# Sheet_Receive.net
KiCad netlist of a schematic drawn in Altium Designer
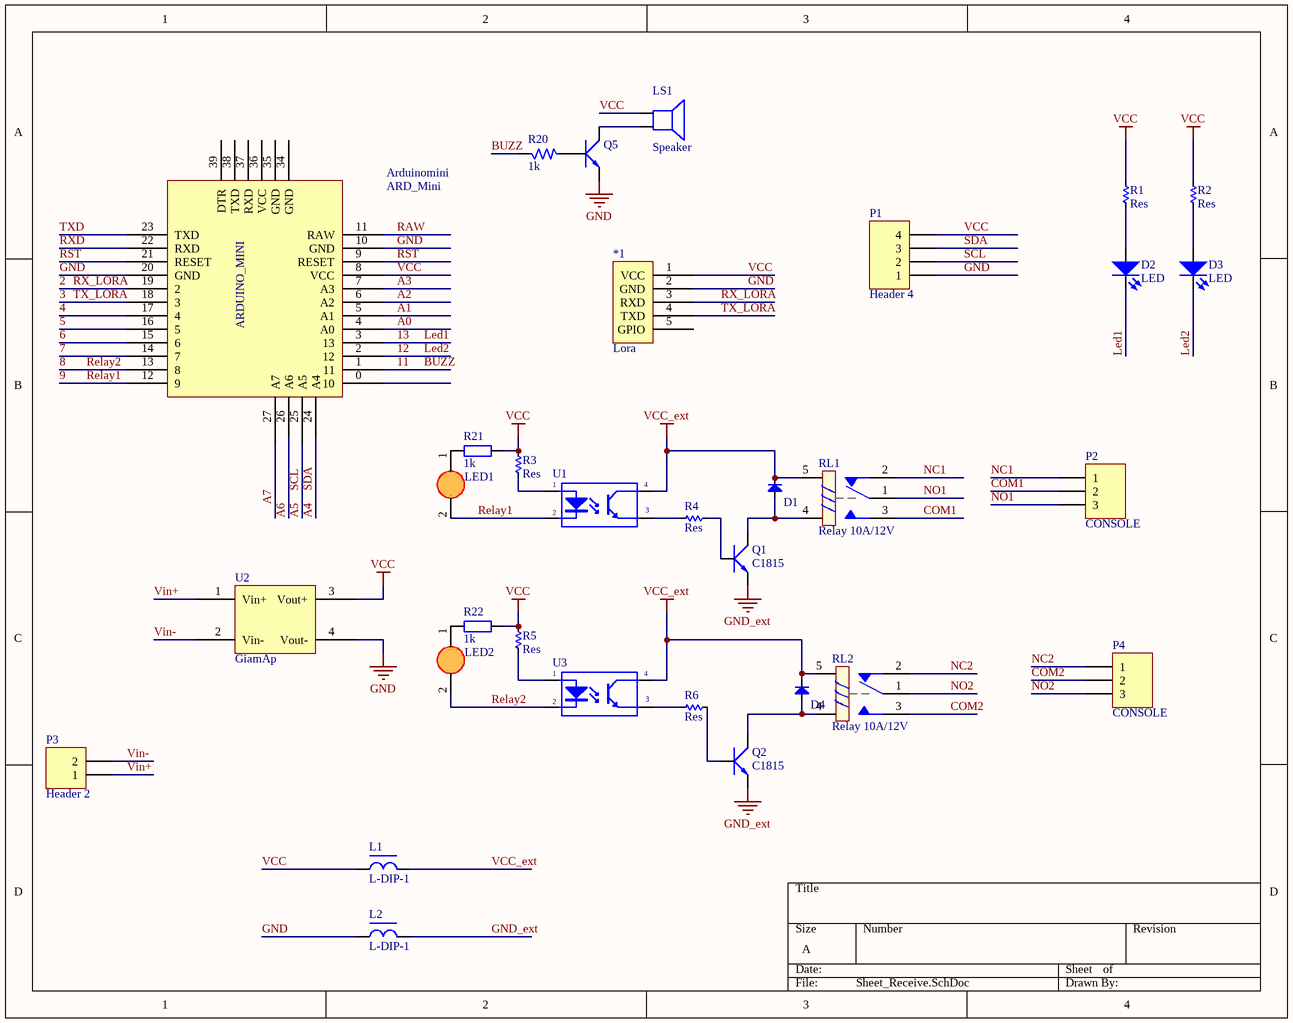
[diagram p0: Sheet_Receive.SchDoc]

(export (version "E")
  (design (tool "Eeschema 10.0.6"))
  (components
    (comp (ref "*1") (value "Lora") (footprint "Lora") (libsource (lib "Nhan") (part "Lora")))
    (comp (ref "Arduinomini")
      (value "ARD_Mini")
      (footprint "Arduino_mini")
      (libsource (lib "smart_Home_lib") (part "Arduino_mini"))
    )
    (comp (ref "D1")
      (value "Diode")
      (footprint "DIO-1A-SMALL")
      (description "Default Diode")
      (fields (field (name "PUBLISHER") "Altium Limited"))
      (libsource (lib "LIBRARY") (part "Diode"))
    )
    (comp (ref "D2")
      (value "LED")
      (footprint "LED-5 GRe")
      (description "LED Single")
      (libsource (lib "Electric4u") (part "LED"))
    )
    (comp (ref "D3")
      (value "LED")
      (footprint "LED-5TRED")
      (description "LED Single")
      (libsource (lib "Electric4u") (part "LED"))
    )
    (comp (ref "D4")
      (value "Diode")
      (footprint "DIO-1A-SMALL")
      (description "Default Diode")
      (fields (field (name "PUBLISHER") "Altium Limited"))
      (libsource (lib "LIBRARY") (part "Diode"))
    )
    (comp (ref "L1")
      (value "L-DIP-1")
      (footprint "L-DIP-M-6.0")
      (description "Inductor")
      (libsource (lib "LIBRARY") (part "L-DIP-1"))
    )
    (comp (ref "L2")
      (value "L-DIP-1")
      (footprint "L-DIP-M-6.0")
      (description "Inductor")
      (libsource (lib "LIBRARY") (part "L-DIP-1"))
    )
    (comp (ref "LED1")
      (value "LED3")
      (footprint "LED3mm")
      (description "LED 3mm")
      (libsource (lib "smart_Home_lib") (part "LED 3mm"))
    )
    (comp (ref "LED2")
      (value "LED3")
      (footprint "LED3mm")
      (description "LED 3mm")
      (libsource (lib "smart_Home_lib") (part "LED 3mm"))
    )
    (comp (ref "LS1")
      (value "Speaker")
      (footprint "SPEAKER")
      (description "Loudspeaker")
      (fields (field (name "PUBLISHER") "Altium Limited"))
      (libsource (lib "LIBRARY") (part "Speaker"))
    )
    (comp (ref "P1")
      (value "Header 4")
      (footprint "HEADER 4PIN")
      (description "Header, 4-Pin")
      (fields (field (name "PUBLISHER") "Altium Limited"))
      (libsource (lib "Electric4u") (part "Header 4"))
    )
    (comp (ref "P2")
      (value "CONSOLE")
      (footprint "HED3T")
      (description "Header, 3-Pin")
      (fields (field (name "PUBLISHER") "Altium Limited"))
      (libsource (lib "Electric4u") (part "Header 3"))
    )
    (comp (ref "P3")
      (value "Header 2")
      (footprint "HED2T")
      (description "Header, 2-Pin")
      (fields (field (name "PUBLISHER") "Altium Limited"))
      (libsource (lib "Electric4u") (part "Header 2"))
    )
    (comp (ref "P4")
      (value "CONSOLE")
      (footprint "HED3T")
      (description "Header, 3-Pin")
      (fields (field (name "PUBLISHER") "Altium Limited"))
      (libsource (lib "Electric4u") (part "Header 3"))
    )
    (comp (ref "Q1")
      (value "C1815")
      (footprint "QTO-92")
      (description "NPN 600mW, ECB")
      (libsource (lib "Electric4u") (part "C1815"))
    )
    (comp (ref "Q2")
      (value "C1815")
      (footprint "QTO-92")
      (description "NPN 600mW, ECB")
      (libsource (lib "Electric4u") (part "C1815"))
    )
    (comp (ref "Q5")
      (value "C1815")
      (footprint "QTO-92")
      (description "NPN 600mW, ECB")
      (libsource (lib "smart_Home_lib") (part "C1815"))
    )
    (comp (ref "R1")
      (value "Res")
      (footprint "RES-1/4W")
      (fields
        (field (name "MANUFACTURER") "Generic Components")
        (field (name "PUBLISHER") "Altium Hobart Technology Centre")
      )
      (libsource (lib "LIBRARY") (part "Res"))
    )
    (comp (ref "R2")
      (value "Res")
      (footprint "RES-1/4W")
      (fields
        (field (name "MANUFACTURER") "Generic Components")
        (field (name "PUBLISHER") "Altium Hobart Technology Centre")
      )
      (libsource (lib "LIBRARY") (part "Res"))
    )
    (comp (ref "R3")
      (value "Res")
      (footprint "RES-1/4W")
      (fields
        (field (name "MANUFACTURER") "Generic Components")
        (field (name "PUBLISHER") "Altium Hobart Technology Centre")
      )
      (libsource (lib "LIBRARY") (part "Res"))
    )
    (comp (ref "R4")
      (value "Res")
      (footprint "RES-1/4W")
      (fields
        (field (name "MANUFACTURER") "Generic Components")
        (field (name "PUBLISHER") "Altium Hobart Technology Centre")
      )
      (libsource (lib "LIBRARY") (part "Res"))
    )
    (comp (ref "R5")
      (value "Res")
      (footprint "RES-1/4W")
      (fields
        (field (name "MANUFACTURER") "Generic Components")
        (field (name "PUBLISHER") "Altium Hobart Technology Centre")
      )
      (libsource (lib "LIBRARY") (part "Res"))
    )
    (comp (ref "R6")
      (value "Res")
      (footprint "RES-1/4W")
      (fields
        (field (name "MANUFACTURER") "Generic Components")
        (field (name "PUBLISHER") "Altium Hobart Technology Centre")
      )
      (libsource (lib "LIBRARY") (part "Res"))
    )
    (comp (ref "R20")
      (value "1k")
      (footprint "R1/4W")
      (description "Res")
      (libsource (lib "my Library") (part "Res"))
    )
    (comp (ref "R21")
      (value "1k")
      (footprint "R1/4W")
      (description "Resistor 1/4W")
      (libsource (lib "smart_Home_lib") (part "R1/4W"))
    )
    (comp (ref "R22")
      (value "1k")
      (footprint "R1/4W")
      (description "Resistor 1/4W")
      (libsource (lib "smart_Home_lib") (part "R1/4W"))
    )
    (comp (ref "RL1")
      (value "Relay 10A/12V")
      (footprint "RELAY 5")
      (description "Relay SPDT,10A - 12VDC 5 Pin")
      (libsource (lib "LIBRARY") (part "Relay 5"))
    )
    (comp (ref "RL2")
      (value "Relay 10A/12V")
      (footprint "RELAY 5")
      (description "Relay SPDT,10A - 12VDC 5 Pin")
      (libsource (lib "LIBRARY") (part "Relay 5"))
    )
    (comp (ref "U1")
      (value "PC817")
      (footprint "DIP4/W.300")
      (description "Single Opto")
      (libsource (lib "smart_Home_lib") (part "PC817"))
    )
    (comp (ref "U2")
      (value "GiamAp")
      (footprint "DC-DC MP1584")
      (libsource (lib "Nhan") (part "DC-DC 7-26 -{gt} 5"))
    )
    (comp (ref "U3")
      (value "PC817")
      (footprint "DIP4/W.300")
      (description "Single Opto")
      (libsource (lib "smart_Home_lib") (part "PC817"))
    )
  )
  (nets
    (net (code "1") (name "/2") (class "Default")
      (node (ref "*1") (pin "3") (pinfunction "RXD_3") (pintype "passive"))
      (node (ref "Arduinomini") (pin "19") (pinfunction "2_19") (pintype "passive"))
    )
    (net (code "2") (name "/3") (class "Default")
      (node (ref "*1") (pin "4") (pinfunction "TXD_4") (pintype "passive"))
      (node (ref "Arduinomini") (pin "18") (pinfunction "3_18") (pintype "passive"))
    )
    (net (code "3") (name "/4") (class "Default")
      (node (ref "Arduinomini") (pin "17") (pinfunction "4_17") (pintype "passive"))
    )
    (net (code "4") (name "/5") (class "Default")
      (node (ref "Arduinomini") (pin "16") (pinfunction "5_16") (pintype "passive"))
    )
    (net (code "5") (name "/6") (class "Default")
      (node (ref "Arduinomini") (pin "15") (pinfunction "6_15") (pintype "passive"))
    )
    (net (code "6") (name "/7") (class "Default")
      (node (ref "Arduinomini") (pin "14") (pinfunction "7_14") (pintype "passive"))
    )
    (net (code "7") (name "/8") (class "Default")
      (node (ref "Arduinomini") (pin "13") (pinfunction "8_13") (pintype "passive"))
      (node (ref "LED2") (pin "2") (pinfunction "K_2") (pintype "passive"))
      (node (ref "U3") (pin "2") (pinfunction "K_2") (pintype "passive"))
    )
    (net (code "8") (name "/9") (class "Default")
      (node (ref "Arduinomini") (pin "12") (pinfunction "9_12") (pintype "passive"))
      (node (ref "LED1") (pin "2") (pinfunction "K_2") (pintype "passive"))
      (node (ref "U1") (pin "2") (pinfunction "K_2") (pintype "passive"))
    )
    (net (code "9") (name "/11") (class "Default")
      (node (ref "Arduinomini") (pin "1") (pinfunction "11_1") (pintype "passive"))
      (node (ref "R20") (pin "1") (pinfunction "1_1") (pintype "passive"))
    )
    (net (code "10") (name "/12") (class "Default")
      (node (ref "Arduinomini") (pin "2") (pinfunction "12_2") (pintype "passive"))
      (node (ref "D3") (pin "2") (pinfunction "2_2") (pintype "passive"))
    )
    (net (code "11") (name "/13") (class "Default")
      (node (ref "Arduinomini") (pin "3") (pinfunction "13_3") (pintype "passive"))
      (node (ref "D2") (pin "2") (pinfunction "2_2") (pintype "passive"))
    )
    (net (code "12") (name "/A0") (class "Default")
      (node (ref "Arduinomini") (pin "4") (pinfunction "A0_4") (pintype "passive"))
    )
    (net (code "13") (name "/A1") (class "Default")
      (node (ref "Arduinomini") (pin "5") (pinfunction "A1_5") (pintype "passive"))
    )
    (net (code "14") (name "/A2") (class "Default")
      (node (ref "Arduinomini") (pin "6") (pinfunction "A2_6") (pintype "passive"))
    )
    (net (code "15") (name "/A3") (class "Default")
      (node (ref "Arduinomini") (pin "7") (pinfunction "A3_7") (pintype "passive"))
    )
    (net (code "16") (name "/A4") (class "Default")
      (node (ref "Arduinomini") (pin "24") (pinfunction "A4_24") (pintype "passive"))
      (node (ref "P1") (pin "3") (pinfunction "3_3") (pintype "passive"))
    )
    (net (code "17") (name "/A5") (class "Default")
      (node (ref "Arduinomini") (pin "25") (pinfunction "A5_25") (pintype "passive"))
      (node (ref "P1") (pin "2") (pinfunction "2_2") (pintype "passive"))
    )
    (net (code "18") (name "/A6") (class "Default")
      (node (ref "Arduinomini") (pin "26") (pinfunction "A6_26") (pintype "passive"))
    )
    (net (code "19") (name "/A7") (class "Default")
      (node (ref "Arduinomini") (pin "27") (pinfunction "A7_27") (pintype "passive"))
    )
    (net (code "20") (name "/COM1") (class "Default")
      (node (ref "P2") (pin "2") (pinfunction "2_2") (pintype "passive"))
      (node (ref "RL1") (pin "3") (pinfunction "3_3") (pintype "passive"))
    )
    (net (code "21") (name "/COM2") (class "Default")
      (node (ref "P4") (pin "2") (pinfunction "2_2") (pintype "passive"))
      (node (ref "RL2") (pin "3") (pinfunction "3_3") (pintype "passive"))
    )
    (net (code "22") (name "/NC1") (class "Default")
      (node (ref "P2") (pin "1") (pinfunction "1_1") (pintype "passive"))
      (node (ref "RL1") (pin "2") (pinfunction "2_2") (pintype "passive"))
    )
    (net (code "23") (name "/NC2") (class "Default")
      (node (ref "P4") (pin "1") (pinfunction "1_1") (pintype "passive"))
      (node (ref "RL2") (pin "2") (pinfunction "2_2") (pintype "passive"))
    )
    (net (code "24") (name "/NO1") (class "Default")
      (node (ref "P2") (pin "3") (pinfunction "3_3") (pintype "passive"))
      (node (ref "RL1") (pin "1") (pinfunction "1_1") (pintype "passive"))
    )
    (net (code "25") (name "/NO2") (class "Default")
      (node (ref "P4") (pin "3") (pinfunction "3_3") (pintype "passive"))
      (node (ref "RL2") (pin "1") (pinfunction "1_1") (pintype "passive"))
    )
    (net (code "26") (name "/RAW") (class "Default")
      (node (ref "Arduinomini") (pin "11") (pinfunction "RAW_11") (pintype "passive"))
    )
    (net (code "27") (name "/RST") (class "Default")
      (node (ref "Arduinomini") (pin "21") (pinfunction "RESET_21") (pintype "passive"))
      (node (ref "Arduinomini") (pin "9") (pinfunction "RESET_9") (pintype "passive"))
    )
    (net (code "28") (name "/RXD") (class "Default")
      (node (ref "Arduinomini") (pin "22") (pinfunction "RXD_22") (pintype "passive"))
    )
    (net (code "29") (name "/TXD") (class "Default")
      (node (ref "Arduinomini") (pin "23") (pinfunction "TXD_23") (pintype "passive"))
    )
    (net (code "30") (name "/Vin+") (class "Default")
      (node (ref "P3") (pin "1") (pinfunction "1_1") (pintype "passive"))
      (node (ref "U2") (pin "1") (pinfunction "Vin+_1") (pintype "passive"))
    )
    (net (code "31") (name "/Vin-") (class "Default")
      (node (ref "P3") (pin "2") (pinfunction "2_2") (pintype "passive"))
      (node (ref "U2") (pin "2") (pinfunction "Vin-_2") (pintype "passive"))
    )
    (net (code "32") (name "GND") (class "Default")
      (node (ref "*1") (pin "2") (pinfunction "GND_2") (pintype "passive"))
      (node (ref "Arduinomini") (pin "10") (pinfunction "GND_10") (pintype "passive"))
      (node (ref "Arduinomini") (pin "20") (pinfunction "GND_20") (pintype "passive"))
      (node (ref "L2") (pin "1") (pinfunction "1_1") (pintype "passive"))
      (node (ref "P1") (pin "1") (pinfunction "1_1") (pintype "passive"))
      (node (ref "Q5") (pin "1") (pinfunction "E_1") (pintype "passive"))
      (node (ref "U2") (pin "4") (pinfunction "Vout-_4") (pintype "passive"))
    )
    (net (code "33") (name "GND_ext") (class "Default")
      (node (ref "L2") (pin "2") (pinfunction "2_2") (pintype "passive"))
      (node (ref "Q1") (pin "1") (pinfunction "E_1") (pintype "passive"))
      (node (ref "Q2") (pin "1") (pinfunction "E_1") (pintype "passive"))
    )
    (net (code "34") (name "Net-(D1-A)") (class "Default")
      (node (ref "D1") (pin "1") (pinfunction "A_1") (pintype "passive"))
      (node (ref "Q1") (pin "2") (pinfunction "C_2") (pintype "passive"))
      (node (ref "RL1") (pin "4") (pinfunction "4_4") (pintype "passive"))
    )
    (net (code "35") (name "Net-(D2-Pad1)") (class "Default")
      (node (ref "D2") (pin "1") (pinfunction "1_1") (pintype "passive"))
      (node (ref "R1") (pin "1") (pinfunction "1_1") (pintype "passive"))
    )
    (net (code "36") (name "Net-(D3-Pad1)") (class "Default")
      (node (ref "D3") (pin "1") (pinfunction "1_1") (pintype "passive"))
      (node (ref "R2") (pin "1") (pinfunction "1_1") (pintype "passive"))
    )
    (net (code "37") (name "Net-(D4-A)") (class "Default")
      (node (ref "D4") (pin "1") (pinfunction "A_1") (pintype "passive"))
      (node (ref "Q2") (pin "2") (pinfunction "C_2") (pintype "passive"))
      (node (ref "RL2") (pin "4") (pinfunction "4_4") (pintype "passive"))
    )
    (net (code "38") (name "Net-(LED1-A)") (class "Default")
      (node (ref "LED1") (pin "1") (pinfunction "A_1") (pintype "passive"))
      (node (ref "R21") (pin "1") (pinfunction "1_1") (pintype "passive"))
    )
    (net (code "39") (name "Net-(LED2-A)") (class "Default")
      (node (ref "LED2") (pin "1") (pinfunction "A_1") (pintype "passive"))
      (node (ref "R22") (pin "1") (pinfunction "1_1") (pintype "passive"))
    )
    (net (code "40") (name "Net-(Q1-B)") (class "Default")
      (node (ref "Q1") (pin "3") (pinfunction "B_3") (pintype "passive"))
      (node (ref "R4") (pin "2") (pinfunction "2_2") (pintype "passive"))
    )
    (net (code "41") (name "Net-(Q2-B)") (class "Default")
      (node (ref "Q2") (pin "3") (pinfunction "B_3") (pintype "passive"))
      (node (ref "R6") (pin "2") (pinfunction "2_2") (pintype "passive"))
    )
    (net (code "42") (name "Net-(Q5-B)") (class "Default")
      (node (ref "Q5") (pin "3") (pinfunction "B_3") (pintype "passive"))
      (node (ref "R20") (pin "2") (pinfunction "2_2") (pintype "passive"))
    )
    (net (code "43") (name "Net-(Q5-C)") (class "Default")
      (node (ref "LS1") (pin "2") (pinfunction "2_2") (pintype "passive"))
      (node (ref "Q5") (pin "2") (pinfunction "C_2") (pintype "passive"))
    )
    (net (code "44") (name "Net-(U1-A)") (class "Default")
      (node (ref "R3") (pin "2") (pinfunction "2_2") (pintype "passive"))
      (node (ref "U1") (pin "1") (pinfunction "A_1") (pintype "passive"))
    )
    (net (code "45") (name "Net-(U1-E)") (class "Default")
      (node (ref "R4") (pin "1") (pinfunction "1_1") (pintype "passive"))
      (node (ref "U1") (pin "3") (pinfunction "E_3") (pintype "passive"))
    )
    (net (code "46") (name "Net-(U3-A)") (class "Default")
      (node (ref "R5") (pin "2") (pinfunction "2_2") (pintype "passive"))
      (node (ref "U3") (pin "1") (pinfunction "A_1") (pintype "passive"))
    )
    (net (code "47") (name "Net-(U3-E)") (class "Default")
      (node (ref "R6") (pin "1") (pinfunction "1_1") (pintype "passive"))
      (node (ref "U3") (pin "3") (pinfunction "E_3") (pintype "passive"))
    )
    (net (code "48") (name "VCC") (class "Default")
      (node (ref "*1") (pin "1") (pinfunction "VCC_1") (pintype "passive"))
      (node (ref "Arduinomini") (pin "8") (pinfunction "VCC_8") (pintype "passive"))
      (node (ref "L1") (pin "1") (pinfunction "1_1") (pintype "passive"))
      (node (ref "LS1") (pin "1") (pinfunction "1_1") (pintype "passive"))
      (node (ref "P1") (pin "4") (pinfunction "4_4") (pintype "passive"))
      (node (ref "R1") (pin "2") (pinfunction "2_2") (pintype "passive"))
      (node (ref "R2") (pin "2") (pinfunction "2_2") (pintype "passive"))
      (node (ref "R21") (pin "2") (pinfunction "2_2") (pintype "passive"))
      (node (ref "R22") (pin "2") (pinfunction "2_2") (pintype "passive"))
      (node (ref "R3") (pin "1") (pinfunction "1_1") (pintype "passive"))
      (node (ref "R5") (pin "1") (pinfunction "1_1") (pintype "passive"))
      (node (ref "U2") (pin "3") (pinfunction "Vout+_3") (pintype "passive"))
    )
    (net (code "49") (name "VCC_ext") (class "Default")
      (node (ref "D1") (pin "2") (pinfunction "K_2") (pintype "passive"))
      (node (ref "D4") (pin "2") (pinfunction "K_2") (pintype "passive"))
      (node (ref "L1") (pin "2") (pinfunction "2_2") (pintype "passive"))
      (node (ref "RL1") (pin "5") (pinfunction "5_5") (pintype "passive"))
      (node (ref "RL2") (pin "5") (pinfunction "5_5") (pintype "passive"))
      (node (ref "U1") (pin "4") (pinfunction "C_4") (pintype "passive"))
      (node (ref "U3") (pin "4") (pinfunction "C_4") (pintype "passive"))
    )
    (net (code "50") (name "unconnected-(*1-GPIO-Pad5)") (class "Default")
      (node (ref "*1") (pin "5") (pinfunction "GPIO_5") (pintype "passive"))
    )
    (net (code "51") (name "unconnected-(Arduinomini-10-Pad0)") (class "Default")
      (node (ref "Arduinomini") (pin "0") (pinfunction "10_0") (pintype "passive"))
    )
    (net (code "52") (name "unconnected-(Arduinomini-DTR-Pad39)") (class "Default")
      (node (ref "Arduinomini") (pin "39") (pinfunction "DTR_39") (pintype "passive"))
    )
    (net (code "53") (name "unconnected-(Arduinomini-GND-Pad34)") (class "Default")
      (node (ref "Arduinomini") (pin "34") (pinfunction "GND_34") (pintype "passive"))
    )
    (net (code "54") (name "unconnected-(Arduinomini-GND-Pad35)") (class "Default")
      (node (ref "Arduinomini") (pin "35") (pinfunction "GND_35") (pintype "passive"))
    )
    (net (code "55") (name "unconnected-(Arduinomini-RXD-Pad37)") (class "Default")
      (node (ref "Arduinomini") (pin "37") (pinfunction "RXD_37") (pintype "passive"))
    )
    (net (code "56") (name "unconnected-(Arduinomini-TXD-Pad38)") (class "Default")
      (node (ref "Arduinomini") (pin "38") (pinfunction "TXD_38") (pintype "passive"))
    )
    (net (code "57") (name "unconnected-(Arduinomini-VCC-Pad36)") (class "Default")
      (node (ref "Arduinomini") (pin "36") (pinfunction "VCC_36") (pintype "passive"))
    )
  )
)
